# untitled.net
KiCad netlist of a schematic drawn in EAGLE
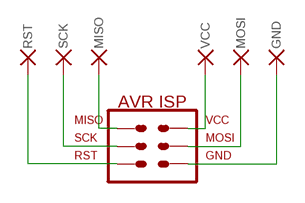
[diagram p0: schematic, sheet 1]

(export (version "E")
  (design (tool "Eeschema 10.0.6"))
  (components
    (comp (ref "GND")
      (value "GND")
      (footprint "eagle-import:POGO_PIN_P50-XX_HORIZONTALLY")
      (libsource (lib "eagle-import") (part "POGO_PIN_P50-XX_HORIZONTALLY"))
    )
    (comp (ref "MISO")
      (value "MISO")
      (footprint "eagle-import:POGO_PIN_P50-XX_HORIZONTALLY")
      (libsource (lib "eagle-import") (part "POGO_PIN_P50-XX_HORIZONTALLY"))
    )
    (comp (ref "MOSI")
      (value "MOSI")
      (footprint "eagle-import:POGO_PIN_P50-XX_HORIZONTALLY")
      (libsource (lib "eagle-import") (part "POGO_PIN_P50-XX_HORIZONTALLY"))
    )
    (comp (ref "RST")
      (value "RST")
      (footprint "eagle-import:POGO_PIN_P50-XX_HORIZONTALLY")
      (libsource (lib "eagle-import") (part "POGO_PIN_P50-XX_HORIZONTALLY"))
    )
    (comp (ref "SCK")
      (value "SCK")
      (footprint "eagle-import:POGO_PIN_P50-XX_HORIZONTALLY")
      (libsource (lib "eagle-import") (part "POGO_PIN_P50-XX_HORIZONTALLY"))
    )
    (comp (ref "VCC")
      (value "VCC")
      (footprint "eagle-import:POGO_PIN_P50-XX_HORIZONTALLY")
      (libsource (lib "eagle-import") (part "POGO_PIN_P50-XX_HORIZONTALLY"))
    )
    (comp (ref "X1")
      (value "AVR-ISP_10X_IDC_LOCK_EDGE_PCB")
      (footprint "eagle-import:AVR-ISP-10_EDGE_PCB")
      (libsource (lib "eagle-import") (part "AVR-ISP_10X_IDC_LOCK_EDGE_PCB"))
    )
  )
  (nets
    (net (code "1") (name "Net-(GND-P)") (class "Default")
      (node (ref "GND") (pin "P$1") (pinfunction "P_P$1") (pintype "passive"))
      (node (ref "X1") (pin "GND") (pinfunction "GND_GND") (pintype "passive"))
      (node (ref "X1") (pin "GND1") (pinfunction "GND_GND1") (pintype "passive"))
      (node (ref "X1") (pin "GND2") (pinfunction "GND_GND2") (pintype "passive"))
      (node (ref "X1") (pin "GND3") (pinfunction "GND_GND3") (pintype "passive"))
    )
    (net (code "2") (name "Net-(MISO-P)") (class "Default")
      (node (ref "MISO") (pin "P$1") (pinfunction "P_P$1") (pintype "passive"))
      (node (ref "X1") (pin "MISO") (pinfunction "MISO_MISO") (pintype "passive"))
    )
    (net (code "3") (name "Net-(MOSI-P)") (class "Default")
      (node (ref "MOSI") (pin "P$1") (pinfunction "P_P$1") (pintype "passive"))
      (node (ref "X1") (pin "MOSI") (pinfunction "MOSI_MOSI") (pintype "passive"))
    )
    (net (code "4") (name "Net-(RST-P)") (class "Default")
      (node (ref "RST") (pin "P$1") (pinfunction "P_P$1") (pintype "passive"))
      (node (ref "X1") (pin "RST") (pinfunction "RST_RST") (pintype "passive"))
    )
    (net (code "5") (name "Net-(SCK-P)") (class "Default")
      (node (ref "SCK") (pin "P$1") (pinfunction "P_P$1") (pintype "passive"))
      (node (ref "X1") (pin "SCK") (pinfunction "SCK_SCK") (pintype "passive"))
    )
    (net (code "6") (name "Net-(VCC-P)") (class "Default")
      (node (ref "VCC") (pin "P$1") (pinfunction "P_P$1") (pintype "passive"))
      (node (ref "X1") (pin "VCC") (pinfunction "VCC_VCC") (pintype "passive"))
    )
  )
)
